# RF_opamp.net
KiCad netlist of a schematic drawn in Altium Designer
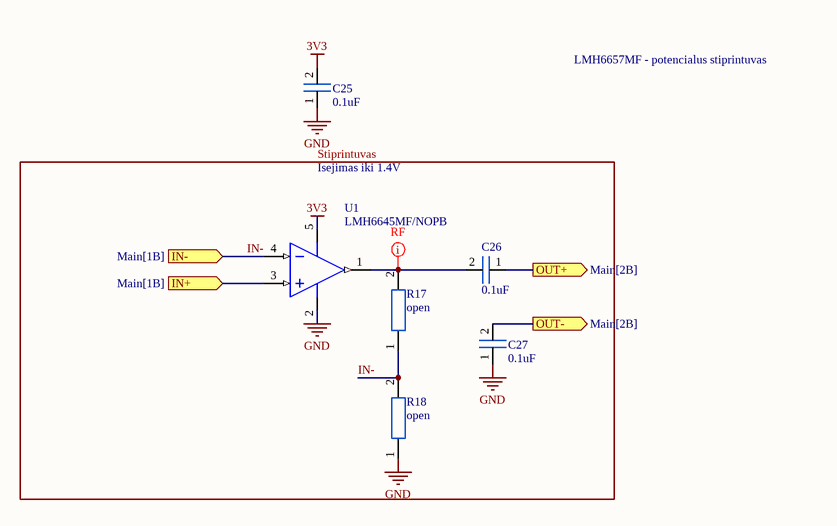
[diagram p0: RF_opamp.SchDoc]

(export (version "E")
  (design (tool "Eeschema 10.0.6"))
  (components
    (comp (ref "C25")
      (value "0.1uF")
      (footprint "0402_footprint")
      (description "0402 capacitor")
      (libsource (lib "Schlib1") (part "Capacitor_0402"))
    )
    (comp (ref "C26")
      (value "0.1uF")
      (footprint "0402_footprint")
      (description "0402 capacitor")
      (libsource (lib "Schlib1") (part "Capacitor_0402"))
    )
    (comp (ref "C27")
      (value "0.1uF")
      (footprint "0402_footprint")
      (description "0402 capacitor")
      (libsource (lib "Schlib1") (part "Capacitor_0402"))
    )
    (comp (ref "R17")
      (value "open")
      (footprint "0402_footprint")
      (libsource (lib "Schlib1") (part "Resistor_0402"))
    )
    (comp (ref "R18")
      (value "open")
      (footprint "0402_footprint")
      (libsource (lib "Schlib1") (part "Resistor_0402"))
    )
    (comp (ref "U1")
      (value "LMH6645MF/NOPB")
      (footprint "DBV0005A_N")
      (fields (field (name "MANUFACTURER") "Texas Instruments"))
      (libsource (lib "Altium Content Vault") (part "AMP-OPA-LM7121-5"))
    )
  )
  (nets
    (net (code "1") (name "/IN+") (class "Default")
      (node (ref "U1") (pin "3") (pinfunction "IN+_3") (pintype "input"))
    )
    (net (code "2") (name "/IN-") (class "Default")
      (node (ref "R17") (pin "1") (pinfunction "1_1") (pintype "passive"))
      (node (ref "R18") (pin "2") (pinfunction "2_2") (pintype "passive"))
      (node (ref "U1") (pin "4") (pinfunction "IN-_4") (pintype "input"))
    )
    (net (code "3") (name "/OUT+") (class "Default")
      (node (ref "C26") (pin "1") (pinfunction "1_1") (pintype "passive"))
    )
    (net (code "4") (name "/OUT-") (class "Default")
      (node (ref "C27") (pin "2") (pinfunction "2_2") (pintype "passive"))
    )
    (net (code "5") (name "3V3") (class "Default")
      (node (ref "C25") (pin "2") (pinfunction "2_2") (pintype "passive"))
      (node (ref "U1") (pin "5") (pinfunction "V+_5") (pintype "power_in"))
    )
    (net (code "6") (name "GND") (class "Default")
      (node (ref "C25") (pin "1") (pinfunction "1_1") (pintype "passive"))
      (node (ref "C27") (pin "1") (pinfunction "1_1") (pintype "passive"))
      (node (ref "R18") (pin "1") (pinfunction "1_1") (pintype "passive"))
      (node (ref "U1") (pin "2") (pinfunction "V-_2") (pintype "power_in"))
    )
    (net (code "7") (name "Net-(U1-OUT)") (class "Default")
      (node (ref "C26") (pin "2") (pinfunction "2_2") (pintype "passive"))
      (node (ref "R17") (pin "2") (pinfunction "2_2") (pintype "passive"))
      (node (ref "U1") (pin "1") (pinfunction "OUT_1") (pintype "output"))
    )
  )
)
